# MC.net
KiCad netlist of a schematic drawn in Altium Designer
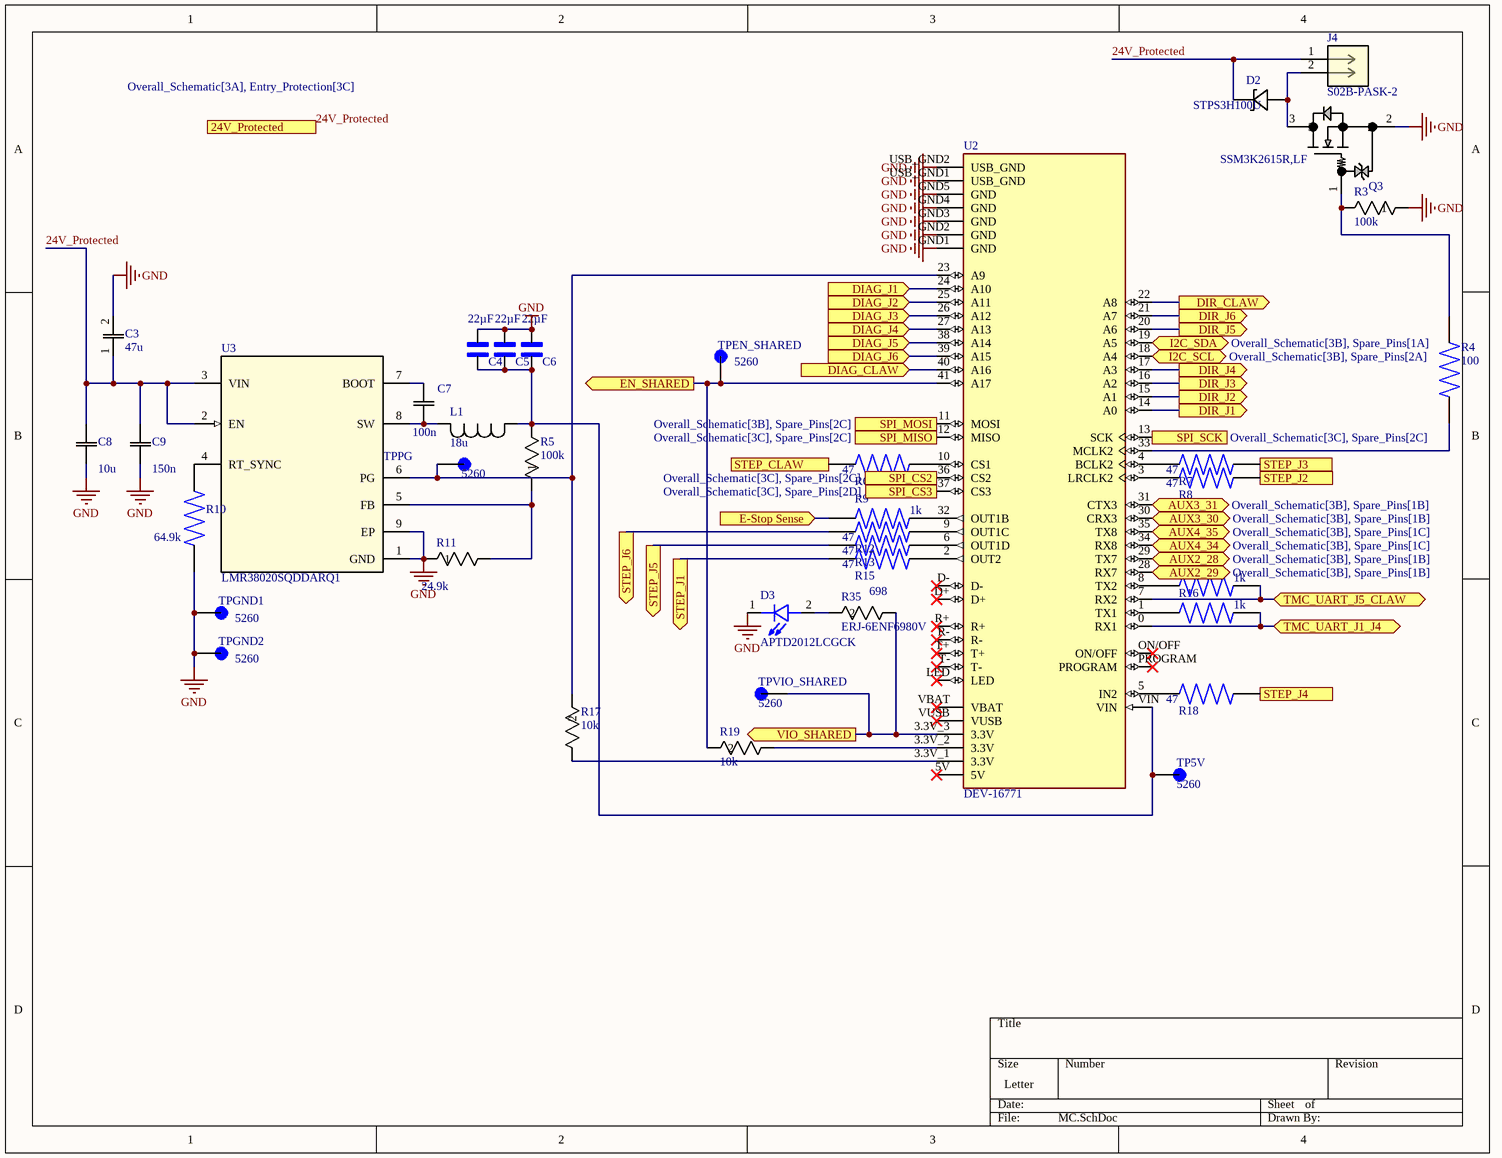
[diagram p0: MC.SchDoc]

(export (version "E")
  (design (tool "Eeschema 10.0.6"))
  (components
    (comp (ref "C3")
      (value "EEUFR1J470")
      (footprint "CAP_EEUFC_63X112_PAN")
      (description "Description")
      (fields
        (field (name "CAPACITANCE") "47u")
        (field (name "COPYRIGHT") "Copyright (C) 2026 Ultra Librarian. All rights reserved.")
      )
      (libsource (lib "EEUFR1J470") (part "EEUFR1J470"))
    )
    (comp (ref "C4")
      (value "CL32B226KAJNNNE")
      (footprint "CAPC3225X270N")
      (description "22 ÂµF Â±10% 25V Ceramic Capacitor X7R 1210 (3225 Metric)")
      (fields (field (name "CAPACITANCE") "22µF") (field (name "MF") "Samsung Electro-Mechanics"))
      (libsource (lib "Chen-Shi Liou") (part "CL32B226KAJNNNE"))
    )
    (comp (ref "C5")
      (value "CL32B226KAJNNNE")
      (footprint "CAPC3225X270N")
      (description "22 ÂµF Â±10% 25V Ceramic Capacitor X7R 1210 (3225 Metric)")
      (fields (field (name "CAPACITANCE") "22µF") (field (name "MF") "Samsung Electro-Mechanics"))
      (libsource (lib "Chen-Shi Liou") (part "CL32B226KAJNNNE"))
    )
    (comp (ref "C6")
      (value "CL32B226KAJNNNE")
      (footprint "CAPC3225X270N")
      (description "22 ÂµF Â±10% 25V Ceramic Capacitor X7R 1210 (3225 Metric)")
      (fields (field (name "CAPACITANCE") "22µF") (field (name "MF") "Samsung Electro-Mechanics"))
      (libsource (lib "Chen-Shi Liou") (part "CL32B226KAJNNNE"))
    )
    (comp (ref "C7")
      (value "CL21B104KCCWPNC")
      (footprint "CAP_CL_21_SAM")
      (description "No Description Available")
      (fields
        (field (name "CAPACITANCE") "100n")
        (field (name "COPYRIGHT") "Copyright (C) 2026 Ultra Librarian. All rights reserved.")
      )
      (libsource (lib "CL21B104KCCWPNC") (part "CL21B104KCCWPNC"))
    )
    (comp (ref "C8")
      (value "22201C106MAT2A")
      (footprint "CAP_22201C106MAT2A_KYO")
      (description "Description")
      (fields
        (field (name "CAPACITANCE") "10u")
        (field (name "COPYRIGHT") "Copyright (C) 2026 Ultra Librarian. All rights reserved.")
      )
      (libsource (lib "22201C106MAT2A") (part "22201C106MAT2A"))
    )
    (comp (ref "C9")
      (value "C0805C154K1RECTU")
      (footprint "CAPC220145_140N_KEM")
      (fields
        (field (name "CAPACITANCE") "150n")
        (field (name "COPYRIGHT") "Copyright (C) 2026 Ultra Librarian. All rights reserved.")
      )
      (libsource (lib "C0805C154K1RECTU") (part "C0805C154K1RECTU"))
    )
    (comp (ref "D2")
      (value "STPS3H100U")
      (footprint "SMB_STM")
      (description "100 V, 3 A Schottky rectifier")
      (fields (field (name "COPYRIGHT") "Copyright (C) 2025 Ultra Librarian. All rights reserved."))
      (libsource (lib "STPS3H100U") (part "STPS3H100U"))
    )
    (comp (ref "D3")
      (value "APTD2012LCGCK")
      (footprint "LED_APTD2012LCGCK")
      (description "Green 570nm LED Indication - Discrete 1.9V 0805 (2012 Metric)")
      (fields (field (name "MF") "Kingbright"))
      (libsource (lib "Chen-Shi Liou") (part "APTD2012LCGCK"))
    )
    (comp (ref "J4")
      (value "S02B-PASK-2")
      (footprint "CONN2_S02B-PASK-2_JST")
      (description "Description")
      (fields (field (name "COPYRIGHT") "Copyright (C) 2026 Ultra Librarian. All rights reserved."))
      (libsource (lib "S02B-PASK-2") (part "S02B-PASK-2"))
    )
    (comp (ref "L1")
      (value "XGL6060-183MEC")
      (footprint "IND_XGL6060_COC")
      (description "Description")
      (fields
        (field (name "INDUCTANCE") "18u")
        (field (name "COPYRIGHT") "Copyright (C) 2026 Ultra Librarian. All rights reserved.")
      )
      (libsource (lib "XGL6060-183MEC") (part "XGL6060-183MEC"))
    )
    (comp (ref "Q3")
      (value "SSM3K2615R,LF")
      (footprint "SOT-23F_TOS")
      (description "N-ch MOSFET, 60 V, 2.0 A, 0.3 Î©@10V, SOT-23F")
      (fields (field (name "COPYRIGHT") "Copyright (C) 2026 Ultra Librarian. All rights reserved."))
      (libsource (lib "Carrier_PBD") (part "SSM3K2615R,LF"))
    )
    (comp (ref "R3")
      (value "ERA-3VEB1003V")
      (footprint "RES_ERA3V,3K_PAN")
      (description "No Description Available")
      (fields
        (field (name "RESISTANCE") "100k")
        (field (name "COPYRIGHT") "Copyright (C) 2026 Ultra Librarian. All rights reserved.")
      )
      (libsource (lib "ERA-3VEB1003V") (part "ERA-3VEB1003V"))
    )
    (comp (ref "R4")
      (value "100")
      (footprint "RES_ERA3VEB1000V")
      (fields (field (name "MP") "ERA3VEB1000V"))
      (libsource (lib "Chen-Shi Liou") (part "ERA3VEB1000V"))
    )
    (comp (ref "R5")
      (value "ERA-3VEB1003V")
      (footprint "RES_ERA3V,3K_PAN")
      (description "No Description Available")
      (fields
        (field (name "RESISTANCE") "100k")
        (field (name "COPYRIGHT") "Copyright (C) 2026 Ultra Librarian. All rights reserved.")
      )
      (libsource (lib "ERA-3VEB1003V") (part "ERA-3VEB1003V"))
    )
    (comp (ref "R6")
      (value "ERA3VEB47R0V")
      (footprint "RES_ERA3VEB47R0V")
      (fields (field (name "RESISTANCE") "47"))
      (libsource (lib "Chen-Shi Liou") (part "ERA3VEB47R0V"))
    )
    (comp (ref "R7")
      (value "ERA3VEB47R0V")
      (footprint "RES_ERA3VEB47R0V")
      (fields (field (name "RESISTANCE") "47"))
      (libsource (lib "Chen-Shi Liou") (part "ERA3VEB47R0V"))
    )
    (comp (ref "R8")
      (value "ERA3VEB47R0V")
      (footprint "RES_ERA3VEB47R0V")
      (fields (field (name "RESISTANCE") "47"))
      (libsource (lib "Chen-Shi Liou") (part "ERA3VEB47R0V"))
    )
    (comp (ref "R9")
      (value "1k")
      (footprint "RES_ERA3VEB1001V")
      (fields (field (name "MP") "ERA3VEB1001V"))
      (libsource (lib "Chen-Shi Liou") (part "ERA3VEB1001V"))
    )
    (comp (ref "R10")
      (value "ERJ3EKF6492V")
      (footprint "RES_ERJ3EKF6492V")
      (fields
        (field (name "MF") "{'manufacturer': u'Panasonic Electronic Components'}")
        (field (name "RESISTANCE") "64.9k")
      )
      (libsource (lib "Chen-Shi Liou") (part "ERJ3EKF6492V"))
    )
    (comp (ref "R11")
      (value "ERA-3VEB2492V")
      (footprint "RES_ERA3V,3K_PAN")
      (description "No Description Available")
      (fields
        (field (name "RESISTANCE") "24.9k")
        (field (name "COPYRIGHT") "Copyright (C) 2026 Ultra Librarian. All rights reserved.")
      )
      (libsource (lib "ERA-3VEB2492V") (part "ERA-3VEB2492V"))
    )
    (comp (ref "R12")
      (value "ERA3VEB47R0V")
      (footprint "RES_ERA3VEB47R0V")
      (fields (field (name "RESISTANCE") "47"))
      (libsource (lib "Chen-Shi Liou") (part "ERA3VEB47R0V"))
    )
    (comp (ref "R13")
      (value "ERA3VEB47R0V")
      (footprint "RES_ERA3VEB47R0V")
      (fields (field (name "RESISTANCE") "47"))
      (libsource (lib "Chen-Shi Liou") (part "ERA3VEB47R0V"))
    )
    (comp (ref "R14")
      (value "1k")
      (footprint "RES_ERA3VEB1001V")
      (fields (field (name "MP") "ERA3VEB1001V"))
      (libsource (lib "Chen-Shi Liou") (part "ERA3VEB1001V"))
    )
    (comp (ref "R15")
      (value "ERA3VEB47R0V")
      (footprint "RES_ERA3VEB47R0V")
      (fields (field (name "RESISTANCE") "47"))
      (libsource (lib "Chen-Shi Liou") (part "ERA3VEB47R0V"))
    )
    (comp (ref "R16")
      (value "1k")
      (footprint "RES_ERA3VEB1001V")
      (fields (field (name "MP") "ERA3VEB1001V"))
      (libsource (lib "Chen-Shi Liou") (part "ERA3VEB1001V"))
    )
    (comp (ref "R17")
      (value "ERJ-3EKF1002V")
      (footprint "RC0603N_PAN")
      (description "SMD-Resistor, 0603, 0,063W, 1%, 100ppm")
      (fields
        (field (name "RESISTANCE") "10k")
        (field (name "COPYRIGHT") "Copyright (C) 2025 Ultra Librarian. All rights reserved.")
      )
      (libsource (lib "ERJ-3EKF1002V") (part "ERJ-3EKF1002V"))
    )
    (comp (ref "R18")
      (value "ERA3VEB47R0V")
      (footprint "RES_ERA3VEB47R0V")
      (fields (field (name "RESISTANCE") "47"))
      (libsource (lib "Chen-Shi Liou") (part "ERA3VEB47R0V"))
    )
    (comp (ref "R19")
      (value "ERJ-3EKF1002V")
      (footprint "RC0603N_PAN")
      (description "SMD-Resistor, 0603, 0,063W, 1%, 100ppm")
      (fields
        (field (name "RESISTANCE") "10k")
        (field (name "COPYRIGHT") "Copyright (C) 2025 Ultra Librarian. All rights reserved.")
      )
      (libsource (lib "ERJ-3EKF1002V") (part "ERJ-3EKF1002V"))
    )
    (comp (ref "R35")
      (value "ERJ-6ENF6980V")
      (footprint "RC0805N_PAN")
      (description "No Description Available")
      (fields
        (field (name "RESISTANCE") "698")
        (field (name "COPYRIGHT") "Copyright (C) 2026 Ultra Librarian. All rights reserved.")
      )
      (libsource (lib "ERJ-6ENF6980V") (part "ERJ-6ENF6980V"))
    )
    (comp (ref "TP5V")
      (value "5260")
      (footprint "KEYSTONE_5260")
      (description "TEST POINT (RED) - MINIATURE")
      (fields (field (name "MF") "Keystone Electronics"))
      (libsource (lib "Chen-Shi Liou") (part "5260"))
    )
    (comp (ref "TPEN_SHARED")
      (value "5260")
      (footprint "KEYSTONE_5260")
      (description "TEST POINT (RED) - MINIATURE")
      (fields (field (name "MF") "Keystone Electronics"))
      (libsource (lib "Chen-Shi Liou") (part "5260"))
    )
    (comp (ref "TPGND1")
      (value "5260")
      (footprint "KEYSTONE_5260")
      (description "TEST POINT (RED) - MINIATURE")
      (fields (field (name "MF") "Keystone Electronics"))
      (libsource (lib "Chen-Shi Liou") (part "5260"))
    )
    (comp (ref "TPGND2")
      (value "5260")
      (footprint "KEYSTONE_5260")
      (description "TEST POINT (RED) - MINIATURE")
      (fields (field (name "MF") "Keystone Electronics"))
      (libsource (lib "Chen-Shi Liou") (part "5260"))
    )
    (comp (ref "TPPG")
      (value "5260")
      (footprint "KEYSTONE_5260")
      (description "TEST POINT (RED) - MINIATURE")
      (fields (field (name "MF") "Keystone Electronics"))
      (libsource (lib "Chen-Shi Liou") (part "5260"))
    )
    (comp (ref "TPVIO_SHARED")
      (value "5260")
      (footprint "KEYSTONE_5260")
      (description "TEST POINT (RED) - MINIATURE")
      (fields (field (name "MF") "Keystone Electronics"))
      (libsource (lib "Chen-Shi Liou") (part "5260"))
    )
    (comp (ref "U2")
      (value "DEV-16771")
      (footprint "MODULE_DEV-16771")
      (description "RT1062 Teensy 4.1 series ARM® Cortex®-M7 MPU Embedded Evaluation Board")
      (fields (field (name "MF") "SparkFun Electronics"))
      (libsource (lib "Chen-Shi Liou") (part "DEV-16771"))
    )
    (comp (ref "U3")
      (value "LMR38020SQDDARQ1")
      (footprint "DDA0008E-IPC_A")
      (fields (field (name "COPYRIGHT") "Copyright (C) 2025 Ultra Librarian. All rights reserved."))
      (libsource (lib "LMR38020SQDDARQ1") (part "LMR38020SQDDARQ1"))
    )
  )
  (nets
    (net (code "1") (name "/24V_Protected") (class "Default")
      (node (ref "C3") (pin "1") (pinfunction "1_1") (pintype "passive"))
      (node (ref "C8") (pin "2") (pinfunction "2_2") (pintype "passive"))
      (node (ref "C9") (pin "2") (pinfunction "2_2") (pintype "passive"))
      (node (ref "D2") (pin "2") (pinfunction "A_2") (pintype "passive"))
      (node (ref "J4") (pin "1") (pinfunction "1_1") (pintype "passive"))
      (node (ref "U3") (pin "2") (pinfunction "EN_2") (pintype "input"))
      (node (ref "U3") (pin "3") (pinfunction "VIN_3") (pintype "power_in"))
    )
    (net (code "2") (name "/AUX2_28") (class "Default")
      (node (ref "U2") (pin "29") (pinfunction "TX7_29") (pintype "bidirectional"))
    )
    (net (code "3") (name "/AUX2_29") (class "Default")
      (node (ref "U2") (pin "28") (pinfunction "RX7_28") (pintype "bidirectional"))
    )
    (net (code "4") (name "/AUX3_30") (class "Default")
      (node (ref "U2") (pin "30") (pinfunction "CRX3_30") (pintype "bidirectional"))
    )
    (net (code "5") (name "/AUX3_31") (class "Default")
      (node (ref "U2") (pin "31") (pinfunction "CTX3_31") (pintype "bidirectional"))
    )
    (net (code "6") (name "/AUX4_34") (class "Default")
      (node (ref "U2") (pin "34") (pinfunction "RX8_34") (pintype "bidirectional"))
    )
    (net (code "7") (name "/AUX4_35") (class "Default")
      (node (ref "U2") (pin "35") (pinfunction "TX8_35") (pintype "bidirectional"))
    )
    (net (code "8") (name "/DIAG_CLAW") (class "Default")
      (node (ref "U2") (pin "40") (pinfunction "A16_40") (pintype "bidirectional"))
    )
    (net (code "9") (name "/DIAG_J1") (class "Default")
      (node (ref "U2") (pin "24") (pinfunction "A10_24") (pintype "bidirectional"))
    )
    (net (code "10") (name "/DIAG_J2") (class "Default")
      (node (ref "U2") (pin "25") (pinfunction "A11_25") (pintype "bidirectional"))
    )
    (net (code "11") (name "/DIAG_J3") (class "Default")
      (node (ref "U2") (pin "26") (pinfunction "A12_26") (pintype "bidirectional"))
    )
    (net (code "12") (name "/DIAG_J4") (class "Default")
      (node (ref "U2") (pin "27") (pinfunction "A13_27") (pintype "bidirectional"))
    )
    (net (code "13") (name "/DIAG_J5") (class "Default")
      (node (ref "U2") (pin "38") (pinfunction "A14_38") (pintype "bidirectional"))
    )
    (net (code "14") (name "/DIAG_J6") (class "Default")
      (node (ref "U2") (pin "39") (pinfunction "A15_39") (pintype "bidirectional"))
    )
    (net (code "15") (name "/DIR_CLAW") (class "Default")
      (node (ref "U2") (pin "22") (pinfunction "A8_22") (pintype "bidirectional"))
    )
    (net (code "16") (name "/DIR_J1") (class "Default")
      (node (ref "U2") (pin "14") (pinfunction "A0_14") (pintype "bidirectional"))
    )
    (net (code "17") (name "/DIR_J2") (class "Default")
      (node (ref "U2") (pin "15") (pinfunction "A1_15") (pintype "bidirectional"))
    )
    (net (code "18") (name "/DIR_J3") (class "Default")
      (node (ref "U2") (pin "16") (pinfunction "A2_16") (pintype "bidirectional"))
    )
    (net (code "19") (name "/DIR_J4") (class "Default")
      (node (ref "U2") (pin "17") (pinfunction "A3_17") (pintype "bidirectional"))
    )
    (net (code "20") (name "/DIR_J5") (class "Default")
      (node (ref "U2") (pin "20") (pinfunction "A6_20") (pintype "bidirectional"))
    )
    (net (code "21") (name "/DIR_J6") (class "Default")
      (node (ref "U2") (pin "21") (pinfunction "A7_21") (pintype "bidirectional"))
    )
    (net (code "22") (name "/E-Stop Sense") (class "Default")
      (node (ref "R9") (pin "1") (pinfunction "1_1") (pintype "passive"))
    )
    (net (code "23") (name "/EN_SHARED") (class "Default")
      (node (ref "R19") (pin "2") (pinfunction "2_2") (pintype "passive"))
      (node (ref "TPEN_SHARED") (pin "1") (pinfunction "TP_1") (pintype "passive"))
      (node (ref "U2") (pin "41") (pinfunction "A17_41") (pintype "bidirectional"))
    )
    (net (code "24") (name "/I2C_SCL") (class "Default")
      (node (ref "U2") (pin "18") (pinfunction "A4_18") (pintype "bidirectional"))
    )
    (net (code "25") (name "/I2C_SDA") (class "Default")
      (node (ref "U2") (pin "19") (pinfunction "A5_19") (pintype "bidirectional"))
    )
    (net (code "26") (name "/SPI_CS2") (class "Default")
      (node (ref "U2") (pin "36") (pinfunction "CS2_36") (pintype "bidirectional"))
    )
    (net (code "27") (name "/SPI_CS3") (class "Default")
      (node (ref "U2") (pin "37") (pinfunction "CS3_37") (pintype "bidirectional"))
    )
    (net (code "28") (name "/SPI_MISO") (class "Default")
      (node (ref "U2") (pin "12") (pinfunction "MISO_12") (pintype "bidirectional"))
    )
    (net (code "29") (name "/SPI_MOSI") (class "Default")
      (node (ref "U2") (pin "11") (pinfunction "MOSI_11") (pintype "bidirectional"))
    )
    (net (code "30") (name "/SPI_SCK") (class "Default")
      (node (ref "U2") (pin "13") (pinfunction "SCK_13") (pintype "bidirectional"))
    )
    (net (code "31") (name "/STEP_CLAW") (class "Default")
      (node (ref "R6") (pin "1") (pinfunction "1_1") (pintype "passive"))
    )
    (net (code "32") (name "/STEP_J1") (class "Default")
      (node (ref "R15") (pin "1") (pinfunction "1_1") (pintype "passive"))
    )
    (net (code "33") (name "/STEP_J2") (class "Default")
      (node (ref "R8") (pin "2") (pinfunction "2_2") (pintype "passive"))
    )
    (net (code "34") (name "/STEP_J3") (class "Default")
      (node (ref "R7") (pin "2") (pinfunction "2_2") (pintype "passive"))
    )
    (net (code "35") (name "/STEP_J4") (class "Default")
      (node (ref "R18") (pin "2") (pinfunction "2_2") (pintype "passive"))
    )
    (net (code "36") (name "/STEP_J5") (class "Default")
      (node (ref "R13") (pin "1") (pinfunction "1_1") (pintype "passive"))
    )
    (net (code "37") (name "/STEP_J6") (class "Default")
      (node (ref "R12") (pin "1") (pinfunction "1_1") (pintype "passive"))
    )
    (net (code "38") (name "/TMC_UART_J1_J4") (class "Default")
      (node (ref "R16") (pin "2") (pinfunction "2_2") (pintype "passive"))
      (node (ref "U2") (pin "0") (pinfunction "RX1_0") (pintype "bidirectional"))
    )
    (net (code "39") (name "/TMC_UART_J5_CLAW") (class "Default")
      (node (ref "R14") (pin "2") (pinfunction "2_2") (pintype "passive"))
      (node (ref "U2") (pin "7") (pinfunction "RX2_7") (pintype "bidirectional"))
    )
    (net (code "40") (name "/VIO_SHARED") (class "Default")
      (node (ref "R35") (pin "1") (pinfunction "1_1") (pintype "passive"))
      (node (ref "TPVIO_SHARED") (pin "1") (pinfunction "TP_1") (pintype "passive"))
      (node (ref "U2") (pin "3.3V_3") (pinfunction "3.3V_3.3V_3") (pintype "power_in"))
    )
    (net (code "41") (name "GND") (class "Default")
      (node (ref "C3") (pin "2") (pinfunction "2_2") (pintype "passive"))
      (node (ref "C4") (pin "2") (pinfunction "2_2") (pintype "passive"))
      (node (ref "C5") (pin "2") (pinfunction "2_2") (pintype "passive"))
      (node (ref "C6") (pin "2") (pinfunction "2_2") (pintype "passive"))
      (node (ref "C8") (pin "1") (pinfunction "1_1") (pintype "passive"))
      (node (ref "C9") (pin "1") (pinfunction "1_1") (pintype "passive"))
      (node (ref "D3") (pin "1") (pinfunction "C_1") (pintype "passive"))
      (node (ref "Q3") (pin "2") (pinfunction "2_2") (pintype "passive"))
      (node (ref "R10") (pin "1") (pinfunction "1_1") (pintype "passive"))
      (node (ref "R11") (pin "1") (pinfunction "1_1") (pintype "passive"))
      (node (ref "R3") (pin "1") (pinfunction "1_1") (pintype "passive"))
      (node (ref "TPGND1") (pin "1") (pinfunction "TP_1") (pintype "passive"))
      (node (ref "TPGND2") (pin "1") (pinfunction "TP_1") (pintype "passive"))
      (node (ref "U2") (pin "GND1") (pinfunction "GND_GND1") (pintype "power_in"))
      (node (ref "U2") (pin "GND2") (pinfunction "GND_GND2") (pintype "power_in"))
      (node (ref "U2") (pin "GND3") (pinfunction "GND_GND3") (pintype "power_in"))
      (node (ref "U2") (pin "GND4") (pinfunction "GND_GND4") (pintype "power_in"))
      (node (ref "U2") (pin "GND5") (pinfunction "GND_GND5") (pintype "power_in"))
      (node (ref "U2") (pin "USB_GND1") (pinfunction "USB_GND_USB_GND1") (pintype "power_in"))
      (node (ref "U2") (pin "USB_GND2") (pinfunction "USB_GND_USB_GND2") (pintype "power_in"))
      (node (ref "U3") (pin "1") (pinfunction "GND_1") (pintype "power_in"))
      (node (ref "U3") (pin "9") (pinfunction "EP_9") (pintype "passive"))
    )
    (net (code "42") (name "Net-(D2-K)") (class "Default")
      (node (ref "D2") (pin "1") (pinfunction "K_1") (pintype "passive"))
      (node (ref "J4") (pin "2") (pinfunction "2_2") (pintype "passive"))
      (node (ref "Q3") (pin "3") (pinfunction "3_3") (pintype "passive"))
    )
    (net (code "43") (name "Net-(D3-A)") (class "Default")
      (node (ref "D3") (pin "2") (pinfunction "A_2") (pintype "passive"))
      (node (ref "R35") (pin "2") (pinfunction "2_2") (pintype "passive"))
    )
    (net (code "44") (name "Net-(Q3-Pad1)") (class "Default")
      (node (ref "Q3") (pin "1") (pinfunction "1_1") (pintype "passive"))
      (node (ref "R3") (pin "2") (pinfunction "2_2") (pintype "passive"))
      (node (ref "R4") (pin "2") (pinfunction "2_2") (pintype "passive"))
    )
    (net (code "45") (name "Net-(R17-Pad1)") (class "Default")
      (node (ref "R17") (pin "1") (pinfunction "1_1") (pintype "passive"))
      (node (ref "U2") (pin "3.3V_1") (pinfunction "3.3V_3.3V_1") (pintype "power_in"))
    )
    (net (code "46") (name "Net-(R19-Pad1)") (class "Default")
      (node (ref "R19") (pin "1") (pinfunction "1_1") (pintype "passive"))
      (node (ref "U2") (pin "3.3V_2") (pinfunction "3.3V_3.3V_2") (pintype "power_in"))
    )
    (net (code "47") (name "Net-(TP5V-TP)") (class "Default")
      (node (ref "C4") (pin "1") (pinfunction "1_1") (pintype "passive"))
      (node (ref "C5") (pin "1") (pinfunction "1_1") (pintype "passive"))
      (node (ref "C6") (pin "1") (pinfunction "1_1") (pintype "passive"))
      (node (ref "L1") (pin "2") (pinfunction "2_2") (pintype "passive"))
      (node (ref "R5") (pin "2") (pinfunction "2_2") (pintype "passive"))
      (node (ref "TP5V") (pin "1") (pinfunction "TP_1") (pintype "passive"))
      (node (ref "U2") (pin "VIN") (pinfunction "VIN_VIN") (pintype "input"))
    )
    (net (code "48") (name "Net-(TPPG-TP)") (class "Default")
      (node (ref "R17") (pin "2") (pinfunction "2_2") (pintype "passive"))
      (node (ref "TPPG") (pin "1") (pinfunction "TP_1") (pintype "passive"))
      (node (ref "U2") (pin "23") (pinfunction "A9_23") (pintype "bidirectional"))
      (node (ref "U3") (pin "6") (pinfunction "PG_6") (pintype "open_collector"))
    )
    (net (code "49") (name "Net-(U2-BCLK2)") (class "Default")
      (node (ref "R7") (pin "1") (pinfunction "1_1") (pintype "passive"))
      (node (ref "U2") (pin "4") (pinfunction "BCLK2_4") (pintype "bidirectional"))
    )
    (net (code "50") (name "Net-(U2-CS1)") (class "Default")
      (node (ref "R6") (pin "2") (pinfunction "2_2") (pintype "passive"))
      (node (ref "U2") (pin "10") (pinfunction "CS1_10") (pintype "bidirectional"))
    )
    (net (code "51") (name "Net-(U2-IN2)") (class "Default")
      (node (ref "R18") (pin "1") (pinfunction "1_1") (pintype "passive"))
      (node (ref "U2") (pin "5") (pinfunction "IN2_5") (pintype "bidirectional"))
    )
    (net (code "52") (name "Net-(U2-LRCLK2)") (class "Default")
      (node (ref "R8") (pin "1") (pinfunction "1_1") (pintype "passive"))
      (node (ref "U2") (pin "3") (pinfunction "LRCLK2_3") (pintype "bidirectional"))
    )
    (net (code "53") (name "Net-(U2-MCLK2)") (class "Default")
      (node (ref "R4") (pin "1") (pinfunction "1_1") (pintype "passive"))
      (node (ref "U2") (pin "33") (pinfunction "MCLK2_33") (pintype "bidirectional"))
    )
    (net (code "54") (name "Net-(U2-OUT1B)") (class "Default")
      (node (ref "R9") (pin "2") (pinfunction "2_2") (pintype "passive"))
      (node (ref "U2") (pin "32") (pinfunction "OUT1B_32") (pintype "output"))
    )
    (net (code "55") (name "Net-(U2-OUT1C)") (class "Default")
      (node (ref "R12") (pin "2") (pinfunction "2_2") (pintype "passive"))
      (node (ref "U2") (pin "9") (pinfunction "OUT1C_9") (pintype "output"))
    )
    (net (code "56") (name "Net-(U2-OUT1D)") (class "Default")
      (node (ref "R13") (pin "2") (pinfunction "2_2") (pintype "passive"))
      (node (ref "U2") (pin "6") (pinfunction "OUT1D_6") (pintype "output"))
    )
    (net (code "57") (name "Net-(U2-OUT2)") (class "Default")
      (node (ref "R15") (pin "2") (pinfunction "2_2") (pintype "passive"))
      (node (ref "U2") (pin "2") (pinfunction "OUT2_2") (pintype "output"))
    )
    (net (code "58") (name "Net-(U2-TX1)") (class "Default")
      (node (ref "R16") (pin "1") (pinfunction "1_1") (pintype "passive"))
      (node (ref "U2") (pin "1") (pinfunction "TX1_1") (pintype "bidirectional"))
    )
    (net (code "59") (name "Net-(U2-TX2)") (class "Default")
      (node (ref "R14") (pin "1") (pinfunction "1_1") (pintype "passive"))
      (node (ref "U2") (pin "8") (pinfunction "TX2_8") (pintype "bidirectional"))
    )
    (net (code "60") (name "Net-(U3-BOOT)") (class "Default")
      (node (ref "C7") (pin "1") (pinfunction "1_1") (pintype "passive"))
      (node (ref "U3") (pin "7") (pinfunction "BOOT_7") (pintype "passive"))
    )
    (net (code "61") (name "Net-(U3-FB)") (class "Default")
      (node (ref "R11") (pin "2") (pinfunction "2_2") (pintype "passive"))
      (node (ref "R5") (pin "1") (pinfunction "1_1") (pintype "passive"))
      (node (ref "U3") (pin "5") (pinfunction "FB_5") (pintype "passive"))
    )
    (net (code "62") (name "Net-(U3-RT_SYNC)") (class "Default")
      (node (ref "R10") (pin "2") (pinfunction "2_2") (pintype "passive"))
      (node (ref "U3") (pin "4") (pinfunction "RT_SYNC_4") (pintype "passive"))
    )
    (net (code "63") (name "Net-(U3-SW)") (class "Default")
      (node (ref "C7") (pin "2") (pinfunction "2_2") (pintype "passive"))
      (node (ref "L1") (pin "1") (pinfunction "1_1") (pintype "passive"))
      (node (ref "U3") (pin "8") (pinfunction "SW_8") (pintype "passive"))
    )
    (net (code "64") (name "unconnected-(U2-Pad5V)") (class "Default")
      (node (ref "U2") (pin "5V") (pinfunction "5V_5V") (pintype "power_in+no_connect"))
    )
    (net (code "65") (name "unconnected-(U2-PadD+)") (class "Default")
      (node (ref "U2") (pin "D+") (pinfunction "D+_D+") (pintype "bidirectional+no_connect"))
    )
    (net (code "66") (name "unconnected-(U2-PadD-)") (class "Default")
      (node (ref "U2") (pin "D-") (pinfunction "D-_D-") (pintype "bidirectional+no_connect"))
    )
    (net (code "67") (name "unconnected-(U2-PadLED)") (class "Default")
      (node (ref "U2") (pin "LED") (pinfunction "LED_LED") (pintype "bidirectional+no_connect"))
    )
    (net (code "68") (name "unconnected-(U2-PadON{slash}OFF)") (class "Default")
      (node (ref "U2") (pin "ON/OFF") (pinfunction "ON/OFF_ON/OFF") (pintype "bidirectional+no_connect"))
    )
    (net (code "69") (name "unconnected-(U2-PadPROGRAM)") (class "Default")
      (node (ref "U2") (pin "PROGRAM") (pinfunction "PROGRAM_PROGRAM") (pintype "bidirectional+no_connect"))
    )
    (net (code "70") (name "unconnected-(U2-PadR+)") (class "Default")
      (node (ref "U2") (pin "R+") (pinfunction "R+_R+") (pintype "bidirectional+no_connect"))
    )
    (net (code "71") (name "unconnected-(U2-PadR-)") (class "Default")
      (node (ref "U2") (pin "R-") (pinfunction "R-_R-") (pintype "bidirectional+no_connect"))
    )
    (net (code "72") (name "unconnected-(U2-PadT+)") (class "Default")
      (node (ref "U2") (pin "T+") (pinfunction "T+_T+") (pintype "bidirectional+no_connect"))
    )
    (net (code "73") (name "unconnected-(U2-PadT-)") (class "Default")
      (node (ref "U2") (pin "T-") (pinfunction "T-_T-") (pintype "bidirectional+no_connect"))
    )
    (net (code "74") (name "unconnected-(U2-PadVBAT)") (class "Default")
      (node (ref "U2") (pin "VBAT") (pinfunction "VBAT_VBAT") (pintype "passive+no_connect"))
    )
    (net (code "75") (name "unconnected-(U2-PadVUSB)") (class "Default")
      (node (ref "U2") (pin "VUSB") (pinfunction "VUSB_VUSB") (pintype "passive+no_connect"))
    )
  )
)
